# 03_-_CIRCUIT.net
KiCad netlist of a schematic drawn in Altium Designer
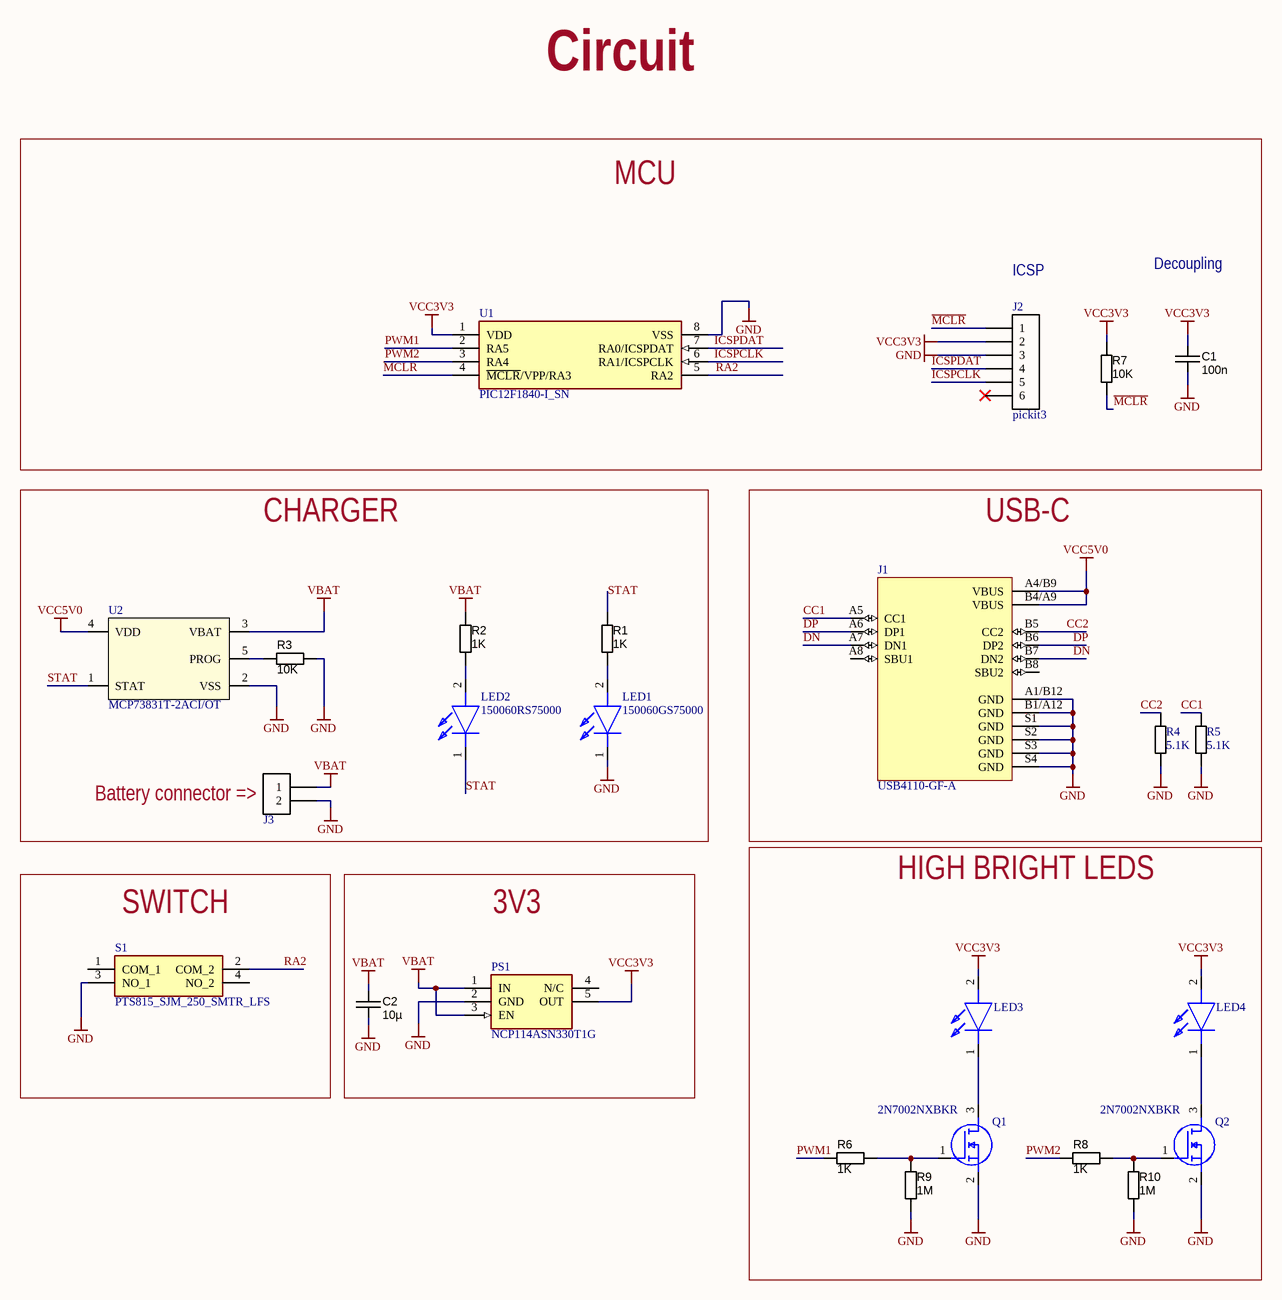
[diagram p0: [03] - CIRCUIT.SchDoc]

(export (version "E")
  (design (tool "Eeschema 10.0.6"))
  (components
    (comp (ref "C1")
      (value "100n")
      (footprint "CAPC1608X90N")
      (description "Capacitor SMD Cer 100nF 10% 50V X7R 0603")
      (fields (field (name "TOLERANCE") "±10%") (field (name "Comment") "approved sub OK"))
      (libsource (lib "PBL - Capacitors") (part "CAPC_100n_0603_X7R_50V_10%"))
    )
    (comp (ref "C2")
      (value "10µ")
      (footprint "CAPC3216X180N")
      (description "Capacitor SMD Cer 10uF 10% 25V X7R 1206")
      (fields (field (name "TOLERANCE") "±10%") (field (name "Comment") "approved sub OK"))
      (libsource (lib "jpnbino") (part "CAPC_10u_1206_25V"))
    )
    (comp (ref "J1")
      (value "USB4110-GF-A")
      (footprint "chico:GCT_USB4110-GF-A")
      (fields (field (name "MF") "GCT") (field (name "DIGI-KEY_PART_NUMBER") "2073-USB4110-GF-A-1-ND"))
      (libsource (lib "chico") (part "USB4110-GF-A"))
    )
    (comp (ref "J2")
      (value "pickit3")
      (footprint "CONN_ICSP")
      (description "CONN PROG PICKIT3 6VIAS")
      (libsource (lib "jpnbino") (part "CONN PROG PICKIT3"))
    )
    (comp (ref "J3")
      (value "S2B-PH-K-S(LF)(SN)")
      (footprint "JST-S2B-PH-K-S_V")
      (fields (field (name "TOLERANCE") "20%"))
      (libsource (lib "jpnbino") (part "CONN JST 2P 2MM"))
    )
    (comp (ref "LED1")
      (value "150060GS75000")
      (footprint "SamacSys:LEDC1608X80N")
      (description "LED")
      (fields (field (name "MOUSER PART NUMBER") "710-150060GS75000"))
      (libsource (lib "*") (part "150060GS75000"))
    )
    (comp (ref "LED2")
      (value "150060RS75000")
      (footprint "SamacSys:LEDC1608X80N")
      (description "LED")
      (fields (field (name "MOUSER PART NUMBER") "710-150060RS75000"))
      (libsource (lib "*") (part "150060RS75000"))
    )
    (comp (ref "LED3")
      (value "S1W0-2835408003-0000003S-00005")
      (footprint "SamacSys:STW8A12DMinJ18CAAll")
      (description "LED")
      (libsource (lib "SamacSys") (part "S1W0-2835408003-0000003S-00005"))
    )
    (comp (ref "LED4")
      (value "S1W0-2835408003-0000003S-00005")
      (footprint "SamacSys:STW8A12DMinJ18CAAll")
      (description "LED")
      (libsource (lib "SamacSys") (part "S1W0-2835408003-0000003S-00005"))
    )
    (comp (ref "PS1")
      (value "NCP114ASN330T1G")
      (footprint "SamacSys:SOT95P275X110-5N")
      (description "Power Supply")
      (fields (field (name "MOUSER PART NUMBER") "863-NCP114ASN330T1G"))
      (libsource (lib "*") (part "NCP114ASN330T1G"))
    )
    (comp (ref "Q1")
      (value "2N7002NXBKR")
      (footprint "SamacSys:SOT95P230X110-3N")
      (description "MOSFET (N-Channel)")
      (fields (field (name "MOUSER PART NUMBER") "771-2N7002NXBKR"))
      (libsource (lib "*") (part "2N7002NXBKR"))
    )
    (comp (ref "Q2")
      (value "2N7002NXBKR")
      (footprint "SamacSys:SOT95P230X110-3N")
      (description "MOSFET (N-Channel)")
      (fields (field (name "MOUSER PART NUMBER") "771-2N7002NXBKR"))
      (libsource (lib "*") (part "2N7002NXBKR"))
    )
    (comp (ref "R1")
      (value "1K")
      (footprint "RESC1608X55N")
      (description "Resistor SMD chip 1k Ohm 0.1W 5% 0603")
      (fields (field (name "TOLERANCE") "±5%") (field (name "Comment") "Thick Film"))
      (libsource (lib "PBL - Resistors") (part "RES_1K_0603_5%"))
    )
    (comp (ref "R2")
      (value "1K")
      (footprint "RESC1608X55N")
      (description "Resistor SMD chip 1k Ohm 0.1W 5% 0603")
      (fields (field (name "TOLERANCE") "±5%") (field (name "Comment") "Thick Film"))
      (libsource (lib "PBL - Resistors") (part "RES_1K_0603_5%"))
    )
    (comp (ref "R3")
      (value "10K")
      (footprint "RESC1608X55N")
      (description "Resistor SMD chip 10k Ohm 0.1W 5% 0603")
      (fields (field (name "TOLERANCE") "±5%") (field (name "Comment") "Thick Film"))
      (libsource (lib "PBL - Resistors") (part "RES_10K_0603_5%"))
    )
    (comp (ref "R4")
      (value "5.1K")
      (footprint "RESC1608X55N")
      (fields (field (name "Comment") "RES 5.1K OHM 5% 1/10W 0603"))
      (libsource (lib "jpnbino") (part "RES 5.1K OHM 5% 1/10W 0603"))
    )
    (comp (ref "R5")
      (value "5.1K")
      (footprint "RESC1608X55N")
      (fields (field (name "Comment") "RES 5.1K OHM 5% 1/10W 0603"))
      (libsource (lib "jpnbino") (part "RES 5.1K OHM 5% 1/10W 0603"))
    )
    (comp (ref "R6")
      (value "1K")
      (footprint "RESC1608X55N")
      (description "Resistor SMD chip 1k Ohm 0.1W 5% 0603")
      (fields (field (name "TOLERANCE") "±5%") (field (name "Comment") "Thick Film"))
      (libsource (lib "RRutledge") (part "RES_1K_0603_5%"))
    )
    (comp (ref "R7")
      (value "10K")
      (footprint "RESC1608X55N")
      (description "Resistor SMD chip 10k Ohm 0.1W 5% 0603")
      (fields (field (name "TOLERANCE") "±5%") (field (name "Comment") "Thick Film"))
      (libsource (lib "") (part "RES_10K_0603_5%_1"))
    )
    (comp (ref "R8")
      (value "1K")
      (footprint "RESC1608X55N")
      (description "Resistor SMD chip 1k Ohm 0.1W 5% 0603")
      (fields (field (name "TOLERANCE") "±5%") (field (name "Comment") "Thick Film"))
      (libsource (lib "RRutledge") (part "RES_1K_0603_5%"))
    )
    (comp (ref "R9")
      (value "1M")
      (footprint "RESC1608X55N")
      (description "Resistor SMD chip 1M Ohm 0.1W 5% 0603")
      (fields (field (name "TOLERANCE") "±5%") (field (name "Comment") "Thick Film"))
      (libsource (lib "RRutledge") (part "RES_1M_0603_5%"))
    )
    (comp (ref "R10")
      (value "1M")
      (footprint "RESC1608X55N")
      (description "Resistor SMD chip 1M Ohm 0.1W 5% 0603")
      (fields (field (name "TOLERANCE") "±5%") (field (name "Comment") "Thick Film"))
      (libsource (lib "RRutledge") (part "RES_1M_0603_5%"))
    )
    (comp (ref "S1")
      (value "PTS815_SJM_250_SMTR_LFS")
      (footprint "SamacSys:PTS815SJM250SMTRLFS")
      (description "Switch")
      (fields
        (field (name "MANUFACTURER_PART_NUMBER") "PTS815 SJM 250 SMTR LFS")
        (field (name "MOUSER PART NUMBER") "611-PTS815SJM250SMTR")
      )
      (libsource (lib "*") (part "PTS815_SJM_250_SMTR_LFS"))
    )
    (comp (ref "U1")
      (value "PIC12F1840-I_SN")
      (footprint "SamacSys:SOIC127P600X175-8N")
      (description "Integrated Circuit")
      (fields
        (field (name "MANUFACTURER_PART_NUMBER") "PIC12F1840-I/SN")
        (field (name "MOUSER PART NUMBER") "579-PIC12F1840-I/SN")
      )
      (libsource (lib "*") (part "PIC12F1840-I_SN"))
    )
    (comp (ref "U2")
      (value "MCP73831T-2ACI/OT")
      (footprint "chico:SOT-23-5_MC_MCH")
      (description "No Description Available")
      (fields (field (name "COPYRIGHT") "Copyright (C) 2018 Accelerated Designs. All rights reserved"))
      (libsource (lib "chico") (part "MCP73831T-2ACI/O"))
    )
  )
  (nets
    (net (code "1") (name "/CC1") (class "Default")
      (node (ref "J1") (pin "A5") (pinfunction "CC1_A5") (pintype "bidirectional"))
      (node (ref "R5") (pin "2") (pinfunction "2_2") (pintype "passive"))
    )
    (net (code "2") (name "/CC2") (class "Default")
      (node (ref "J1") (pin "B5") (pinfunction "CC2_B5") (pintype "bidirectional"))
      (node (ref "R4") (pin "2") (pinfunction "2_2") (pintype "passive"))
    )
    (net (code "3") (name "/DN") (class "Default")
      (node (ref "J1") (pin "A7") (pinfunction "DN1_A7") (pintype "bidirectional"))
      (node (ref "J1") (pin "B7") (pinfunction "DN2_B7") (pintype "bidirectional"))
    )
    (net (code "4") (name "/DP") (class "Default")
      (node (ref "J1") (pin "A6") (pinfunction "DP1_A6") (pintype "bidirectional"))
      (node (ref "J1") (pin "B6") (pinfunction "DP2_B6") (pintype "bidirectional"))
    )
    (net (code "5") (name "/ICSPCLK") (class "Default")
      (node (ref "J2") (pin "5") (pinfunction "5_5") (pintype "passive"))
      (node (ref "U1") (pin "6") (pinfunction "RA1/ICSPCLK_6") (pintype "input"))
    )
    (net (code "6") (name "/ICSPDAT") (class "Default")
      (node (ref "J2") (pin "4") (pinfunction "4_4") (pintype "passive"))
      (node (ref "U1") (pin "7") (pinfunction "RA0/ICSPDAT_7") (pintype "input"))
    )
    (net (code "7") (name "/PWM1") (class "Default")
      (node (ref "R6") (pin "1") (pinfunction "1_1") (pintype "passive"))
      (node (ref "U1") (pin "2") (pinfunction "RA5_2") (pintype "passive"))
    )
    (net (code "8") (name "/PWM2") (class "Default")
      (node (ref "R8") (pin "1") (pinfunction "1_1") (pintype "passive"))
      (node (ref "U1") (pin "3") (pinfunction "RA4_3") (pintype "passive"))
    )
    (net (code "9") (name "/RA2") (class "Default")
      (node (ref "S1") (pin "2") (pinfunction "COM_2_2") (pintype "passive"))
      (node (ref "U1") (pin "5") (pinfunction "RA2_5") (pintype "passive"))
    )
    (net (code "10") (name "/STAT") (class "Default")
      (node (ref "LED2") (pin "1") (pinfunction "K_1") (pintype "passive"))
      (node (ref "R1") (pin "1") (pinfunction "1_1") (pintype "passive"))
      (node (ref "U2") (pin "1") (pinfunction "STAT_1") (pintype "passive"))
    )
    (net (code "11") (name "/~{MCLR}") (class "Default")
      (node (ref "J2") (pin "1") (pinfunction "1_1") (pintype "passive"))
      (node (ref "R7") (pin "2") (pinfunction "2_2") (pintype "passive"))
      (node (ref "U1") (pin "4") (pinfunction "~{MCLR}/VPP/RA3_4") (pintype "passive"))
    )
    (net (code "12") (name "GND") (class "Default")
      (node (ref "C1") (pin "1") (pintype "passive"))
      (node (ref "C2") (pin "2") (pintype "passive"))
      (node (ref "J1") (pin "A1/B12") (pinfunction "GND_A1/B12") (pintype "power_in"))
      (node (ref "J1") (pin "B1/A12") (pinfunction "GND_B1/A12") (pintype "power_in"))
      (node (ref "J1") (pin "S1") (pinfunction "GND_S1") (pintype "power_in"))
      (node (ref "J1") (pin "S2") (pinfunction "GND_S2") (pintype "power_in"))
      (node (ref "J1") (pin "S3") (pinfunction "GND_S3") (pintype "power_in"))
      (node (ref "J1") (pin "S4") (pinfunction "GND_S4") (pintype "power_in"))
      (node (ref "J2") (pin "3") (pinfunction "3_3") (pintype "passive"))
      (node (ref "J3") (pin "2") (pinfunction "2_2") (pintype "passive"))
      (node (ref "LED1") (pin "1") (pinfunction "K_1") (pintype "passive"))
      (node (ref "PS1") (pin "2") (pinfunction "GND_2") (pintype "power_in"))
      (node (ref "Q1") (pin "2") (pinfunction "S_2") (pintype "passive"))
      (node (ref "Q2") (pin "2") (pinfunction "S_2") (pintype "passive"))
      (node (ref "R10") (pin "2") (pinfunction "2_2") (pintype "passive"))
      (node (ref "R3") (pin "2") (pinfunction "2_2") (pintype "passive"))
      (node (ref "R4") (pin "1") (pinfunction "1_1") (pintype "passive"))
      (node (ref "R5") (pin "1") (pinfunction "1_1") (pintype "passive"))
      (node (ref "R9") (pin "2") (pinfunction "2_2") (pintype "passive"))
      (node (ref "S1") (pin "3") (pinfunction "NO_1_3") (pintype "passive"))
      (node (ref "U1") (pin "8") (pinfunction "VSS_8") (pintype "power_in"))
      (node (ref "U2") (pin "2") (pinfunction "VSS_2") (pintype "passive"))
    )
    (net (code "13") (name "Net-(LED1-A)") (class "Default")
      (node (ref "LED1") (pin "2") (pinfunction "A_2") (pintype "passive"))
      (node (ref "R1") (pin "2") (pinfunction "2_2") (pintype "passive"))
    )
    (net (code "14") (name "Net-(LED2-A)") (class "Default")
      (node (ref "LED2") (pin "2") (pinfunction "A_2") (pintype "passive"))
      (node (ref "R2") (pin "2") (pinfunction "2_2") (pintype "passive"))
    )
    (net (code "15") (name "Net-(LED3-K)") (class "Default")
      (node (ref "LED3") (pin "1") (pinfunction "K_1") (pintype "passive"))
      (node (ref "Q1") (pin "3") (pinfunction "D_3") (pintype "passive"))
    )
    (net (code "16") (name "Net-(LED4-K)") (class "Default")
      (node (ref "LED4") (pin "1") (pinfunction "K_1") (pintype "passive"))
      (node (ref "Q2") (pin "3") (pinfunction "D_3") (pintype "passive"))
    )
    (net (code "17") (name "Net-(Q1-G)") (class "Default")
      (node (ref "Q1") (pin "1") (pinfunction "G_1") (pintype "passive"))
      (node (ref "R6") (pin "2") (pinfunction "2_2") (pintype "passive"))
      (node (ref "R9") (pin "1") (pinfunction "1_1") (pintype "passive"))
    )
    (net (code "18") (name "Net-(Q2-G)") (class "Default")
      (node (ref "Q2") (pin "1") (pinfunction "G_1") (pintype "passive"))
      (node (ref "R10") (pin "1") (pinfunction "1_1") (pintype "passive"))
      (node (ref "R8") (pin "2") (pinfunction "2_2") (pintype "passive"))
    )
    (net (code "19") (name "Net-(U2-PROG)") (class "Default")
      (node (ref "R3") (pin "1") (pinfunction "1_1") (pintype "passive"))
      (node (ref "U2") (pin "5") (pinfunction "PROG_5") (pintype "passive"))
    )
    (net (code "20") (name "VBAT") (class "Default")
      (node (ref "C2") (pin "1") (pintype "passive"))
      (node (ref "J3") (pin "1") (pinfunction "1_1") (pintype "passive"))
      (node (ref "PS1") (pin "1") (pinfunction "IN_1") (pintype "power_in"))
      (node (ref "PS1") (pin "3") (pinfunction "EN_3") (pintype "input"))
      (node (ref "R2") (pin "1") (pinfunction "1_1") (pintype "passive"))
      (node (ref "U2") (pin "3") (pinfunction "VBAT_3") (pintype "passive"))
    )
    (net (code "21") (name "VCC3V3") (class "Default")
      (node (ref "C1") (pin "2") (pintype "passive"))
      (node (ref "J2") (pin "2") (pinfunction "2_2") (pintype "passive"))
      (node (ref "LED3") (pin "2") (pinfunction "A_2") (pintype "passive"))
      (node (ref "LED4") (pin "2") (pinfunction "A_2") (pintype "passive"))
      (node (ref "PS1") (pin "5") (pinfunction "OUT_5") (pintype "power_in"))
      (node (ref "R7") (pin "1") (pinfunction "1_1") (pintype "passive"))
      (node (ref "U1") (pin "1") (pinfunction "VDD_1") (pintype "power_in"))
    )
    (net (code "22") (name "VCC5V0") (class "Default")
      (node (ref "J1") (pin "A4/B9") (pinfunction "VBUS_A4/B9") (pintype "power_in"))
      (node (ref "J1") (pin "B4/A9") (pinfunction "VBUS_B4/A9") (pintype "power_in"))
      (node (ref "U2") (pin "4") (pinfunction "VDD_4") (pintype "passive"))
    )
    (net (code "23") (name "unconnected-(J1-SBU1-PadA8)") (class "Default")
      (node (ref "J1") (pin "A8") (pinfunction "SBU1_A8") (pintype "bidirectional"))
    )
    (net (code "24") (name "unconnected-(J1-SBU2-PadB8)") (class "Default")
      (node (ref "J1") (pin "B8") (pinfunction "SBU2_B8") (pintype "bidirectional"))
    )
    (net (code "25") (name "unconnected-(J2-Pad6)") (class "Default")
      (node (ref "J2") (pin "6") (pinfunction "6_6") (pintype "passive+no_connect"))
    )
    (net (code "26") (name "unconnected-(PS1-N{slash}C-Pad4)") (class "Default")
      (node (ref "PS1") (pin "4") (pinfunction "N/C_4") (pintype "passive"))
    )
    (net (code "27") (name "unconnected-(S1-COM_1-Pad1)") (class "Default")
      (node (ref "S1") (pin "1") (pinfunction "COM_1_1") (pintype "passive"))
    )
    (net (code "28") (name "unconnected-(S1-NO_2-Pad4)") (class "Default")
      (node (ref "S1") (pin "4") (pinfunction "NO_2_4") (pintype "passive"))
    )
  )
)
